# kmetria.net
KiCad netlist of a schematic drawn in Altium Designer
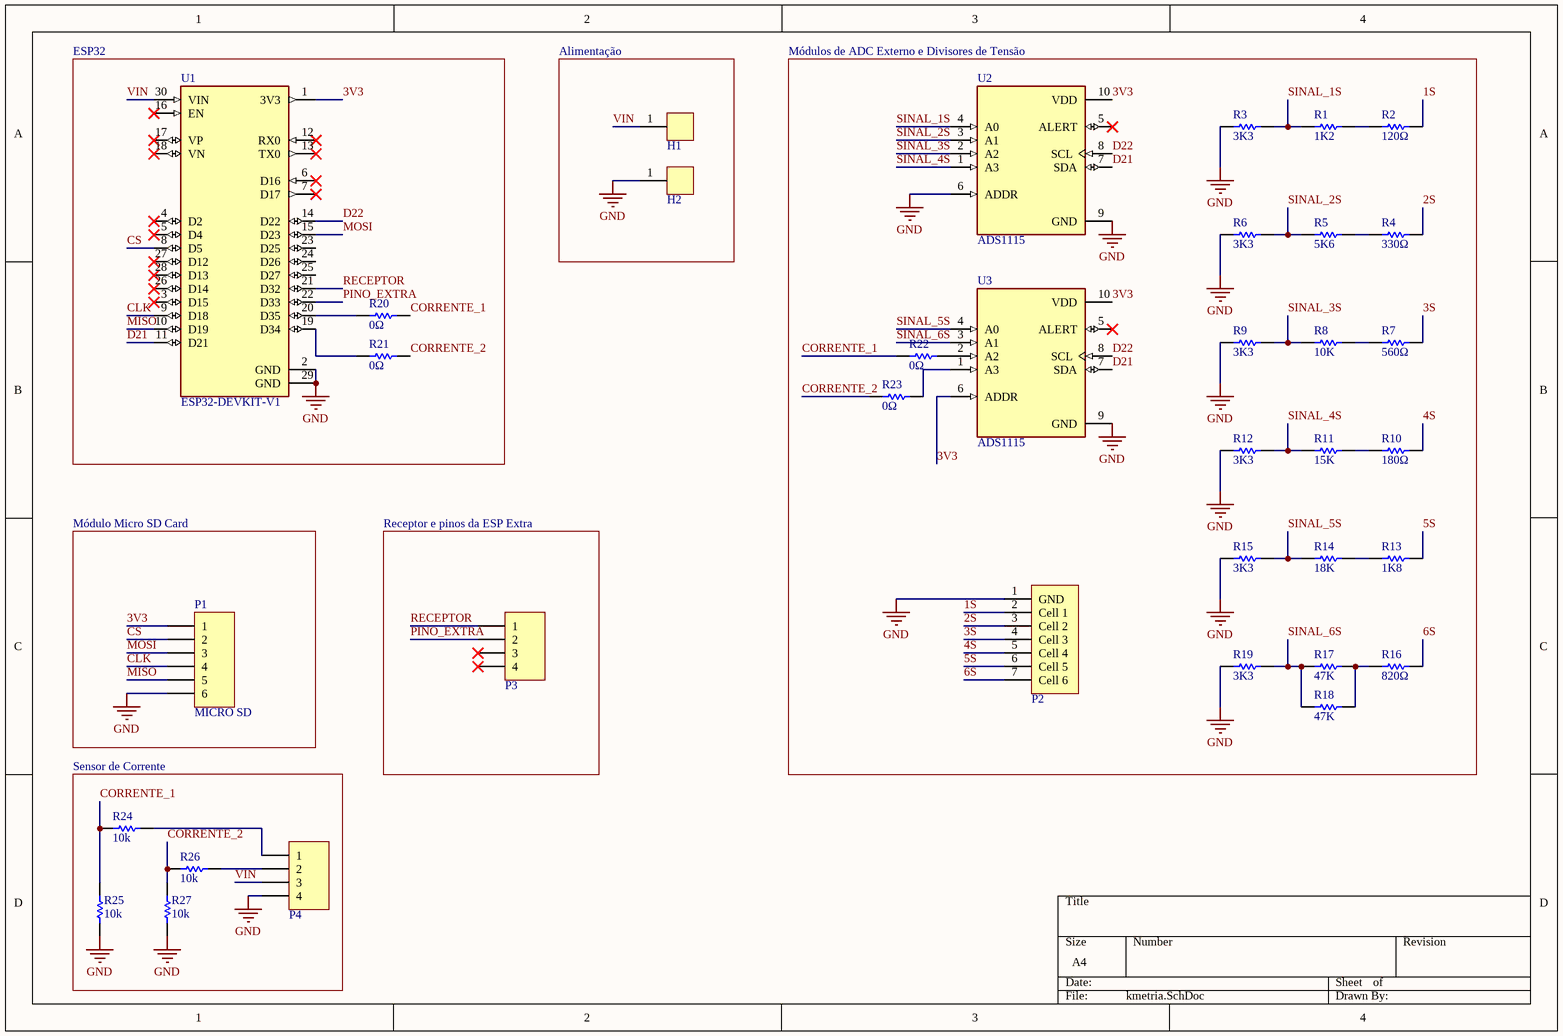
[diagram p0: kmetria.SchDoc]

(export (version "E")
  (design (tool "Eeschema 10.0.6"))
  (components
    (comp (ref "H1")
      (value "Hole")
      (footprint "Hole 1x1")
      (description "General Purpose hole")
      (libsource (lib "kmetria") (part "Hole"))
    )
    (comp (ref "H2")
      (value "Hole")
      (footprint "Hole 1x1")
      (description "General Purpose hole")
      (libsource (lib "kmetria") (part "Hole"))
    )
    (comp (ref "P1")
      (value "MICRO SD")
      (footprint "HDR1X6")
      (description "Headers & Wire Housings 36Pin 2mm Spacing Single Row Hdrs, 5pc")
      (fields
        (field (name "MANUFACTURER") "Molex, LLC")
        (field (name "MANUFACTURER PART NUMBER") "0022284360")
      )
      (libsource (lib "kmetria") (part "Header Male 1x6"))
    )
    (comp (ref "P2")
      (value "Header Male 1x7")
      (footprint "HDR MALE 1x7")
      (description "Headers & Wire Housings 40Pin 2mm Spacing Single Row Hdrs, 5pc")
      (fields (field (name "MANUFACTURER") "Cromax") (field (name "MANUFACTURER PART NUMBER") "IMP10327"))
      (libsource (lib "kmetria") (part "Header Male 1x7"))
    )
    (comp (ref "P3")
      (value "Header 1x4")
      (footprint "HDR MALE 1x4")
      (description "Headers & Wire Housings 40Pin 2mm Spacing Single Row Hdrs, 5pc")
      (fields (field (name "MANUFACTURER") "Cromax") (field (name "MANUFACTURER PART NUMBER") "IMP10327"))
      (libsource (lib "kmetria") (part "Header 1x4"))
    )
    (comp (ref "P4")
      (value "Header 1x4")
      (footprint "HDR MALE 1x4")
      (description "Headers & Wire Housings 40Pin 2mm Spacing Single Row Hdrs, 5pc")
      (fields (field (name "MANUFACTURER") "Cromax") (field (name "MANUFACTURER PART NUMBER") "IMP10327"))
      (libsource (lib "kmetria") (part "Header 1x4"))
    )
    (comp (ref "R1")
      (value "1K2")
      (footprint "RESISTOR 0805")
      (description "RES SMD 5% 0805")
      (fields (field (name "TOLERANCE") "±5%"))
      (libsource (lib "kmetria") (part "RES SMD 5% 0805"))
    )
    (comp (ref "R2")
      (value "120Ω")
      (footprint "RESISTOR 0805")
      (description "RES SMD 5% 0805")
      (fields (field (name "TOLERANCE") "±5%"))
      (libsource (lib "kmetria") (part "RES SMD 5% 0805"))
    )
    (comp (ref "R3")
      (value "3K3")
      (footprint "RESISTOR 0805")
      (description "Thick Film Resistors - SMD 0603 5%")
      (fields
        (field (name "MANUFACTURER") "Yageo")
        (field (name "MANUFACTURER PART NUMBER") "RC0603JR-071R8L")
      )
      (libsource (lib "kmetria") (part "RES 5% 0603"))
    )
    (comp (ref "R4")
      (value "330Ω")
      (footprint "RESISTOR 0805")
      (description "Thick Film Resistors - SMD 0603 5%")
      (fields
        (field (name "MANUFACTURER") "Yageo")
        (field (name "MANUFACTURER PART NUMBER") "RC0603JR-071R8L")
      )
      (libsource (lib "kmetria") (part "RES 5% 0603"))
    )
    (comp (ref "R5")
      (value "5K6")
      (footprint "RESISTOR 0805")
      (description "RES SMD 5% 0805")
      (fields (field (name "TOLERANCE") "±5%"))
      (libsource (lib "kmetria") (part "RES SMD 5% 0805"))
    )
    (comp (ref "R6")
      (value "3K3")
      (footprint "RESISTOR 0805")
      (description "Thick Film Resistors - SMD 0603 5%")
      (fields
        (field (name "MANUFACTURER") "Yageo")
        (field (name "MANUFACTURER PART NUMBER") "RC0603JR-071R8L")
      )
      (libsource (lib "kmetria") (part "RES 5% 0603"))
    )
    (comp (ref "R7")
      (value "560Ω")
      (footprint "RESISTOR 0805")
      (description "RES SMD 5% 0805")
      (fields (field (name "TOLERANCE") "±5%"))
      (libsource (lib "kmetria") (part "RES SMD 5% 0805"))
    )
    (comp (ref "R8")
      (value "10K")
      (footprint "RESISTOR 0805")
      (description "RES SMD 5% 0805")
      (fields (field (name "TOLERANCE") "±5%"))
      (libsource (lib "kmetria") (part "RES SMD 5% 0805"))
    )
    (comp (ref "R9")
      (value "3K3")
      (footprint "RESISTOR 0805")
      (description "Thick Film Resistors - SMD 0603 5%")
      (fields
        (field (name "MANUFACTURER") "Yageo")
        (field (name "MANUFACTURER PART NUMBER") "RC0603JR-071R8L")
      )
      (libsource (lib "kmetria") (part "RES 5% 0603"))
    )
    (comp (ref "R10")
      (value "180Ω")
      (footprint "RESISTOR 0805")
      (description "Thick Film Resistors - SMD 0603 5%")
      (fields
        (field (name "MANUFACTURER") "Yageo")
        (field (name "MANUFACTURER PART NUMBER") "RC0603JR-071R8L")
      )
      (libsource (lib "kmetria") (part "RES 5% 0603"))
    )
    (comp (ref "R11")
      (value "15K")
      (footprint "RESISTOR 0805")
      (description "RES SMD 5% 0805")
      (fields (field (name "TOLERANCE") "±5%"))
      (libsource (lib "kmetria") (part "RES SMD 5% 0805"))
    )
    (comp (ref "R12")
      (value "3K3")
      (footprint "RESISTOR 0805")
      (description "Thick Film Resistors - SMD 0603 5%")
      (fields
        (field (name "MANUFACTURER") "Yageo")
        (field (name "MANUFACTURER PART NUMBER") "RC0603JR-071R8L")
      )
      (libsource (lib "kmetria") (part "RES 5% 0603"))
    )
    (comp (ref "R13")
      (value "1K8")
      (footprint "RESISTOR 0805")
      (description "RES SMD 5% 0805")
      (fields (field (name "TOLERANCE") "±5%"))
      (libsource (lib "kmetria") (part "RES SMD 5% 0805"))
    )
    (comp (ref "R14")
      (value "18K")
      (footprint "RESISTOR 0805")
      (description "Chip Resistor, 1 KOhm, +/- 1%, 0.25 W, -55 to 155 degC, 1206 (3216 Metric)")
      (fields (field (name "Comment") "Resistor 1k +/-1% 1206 250 mW"))
      (libsource (lib "kmetria") (part "RES 1206"))
    )
    (comp (ref "R15")
      (value "3K3")
      (footprint "RESISTOR 0805")
      (description "Thick Film Resistors - SMD 0603 5%")
      (fields
        (field (name "MANUFACTURER") "Yageo")
        (field (name "MANUFACTURER PART NUMBER") "RC0603JR-071R8L")
      )
      (libsource (lib "kmetria") (part "RES 5% 0603"))
    )
    (comp (ref "R16")
      (value "820Ω")
      (footprint "RESISTOR 0805")
      (description "RES SMD 5% 0805")
      (fields (field (name "TOLERANCE") "±5%"))
      (libsource (lib "kmetria") (part "RES SMD 5% 0805"))
    )
    (comp (ref "R17")
      (value "47K")
      (footprint "RESISTOR 0805")
      (description "Thick Film Resistors - SMD 0603 5%")
      (fields
        (field (name "MANUFACTURER") "Yageo")
        (field (name "MANUFACTURER PART NUMBER") "RC0603JR-071R8L")
      )
      (libsource (lib "kmetria") (part "RES 5% 0603"))
    )
    (comp (ref "R18")
      (value "47K")
      (footprint "RESISTOR 0805")
      (description "Thick Film Resistors - SMD 0603 5%")
      (fields
        (field (name "MANUFACTURER") "Yageo")
        (field (name "MANUFACTURER PART NUMBER") "RC0603JR-071R8L")
      )
      (libsource (lib "kmetria") (part "RES 5% 0603"))
    )
    (comp (ref "R19")
      (value "3K3")
      (footprint "RESISTOR 0805")
      (description "Thick Film Resistors - SMD 0603 5%")
      (fields
        (field (name "MANUFACTURER") "Yageo")
        (field (name "MANUFACTURER PART NUMBER") "RC0603JR-071R8L")
      )
      (libsource (lib "kmetria") (part "RES 5% 0603"))
    )
    (comp (ref "R20")
      (value "0Ω")
      (footprint "RESISTOR 0805")
      (description "Thick Film Resistors - SMD 0603 5%")
      (fields
        (field (name "MANUFACTURER") "Yageo")
        (field (name "MANUFACTURER PART NUMBER") "RC0603JR-071R8L")
      )
      (libsource (lib "kmetria") (part "RES 5% 0603"))
    )
    (comp (ref "R21")
      (value "0Ω")
      (footprint "RESISTOR 0805")
      (description "Thick Film Resistors - SMD 0603 5%")
      (fields
        (field (name "MANUFACTURER") "Yageo")
        (field (name "MANUFACTURER PART NUMBER") "RC0603JR-071R8L")
      )
      (libsource (lib "kmetria") (part "RES 5% 0603"))
    )
    (comp (ref "R22")
      (value "0Ω")
      (footprint "RESISTOR 0805")
      (description "Thick Film Resistors - SMD 0603 5%")
      (fields
        (field (name "MANUFACTURER") "Yageo")
        (field (name "MANUFACTURER PART NUMBER") "RC0603JR-071R8L")
      )
      (libsource (lib "kmetria") (part "RES 5% 0603"))
    )
    (comp (ref "R23")
      (value "0Ω")
      (footprint "RESISTOR 0805")
      (description "Thick Film Resistors - SMD 0603 5%")
      (fields
        (field (name "MANUFACTURER") "Yageo")
        (field (name "MANUFACTURER PART NUMBER") "RC0603JR-071R8L")
      )
      (libsource (lib "kmetria") (part "RES 5% 0603"))
    )
    (comp (ref "R24")
      (value "10k")
      (footprint "RESISTOR 0805")
      (description "RES SMD 5% 0805")
      (fields (field (name "TOLERANCE") "±5%"))
      (libsource (lib "kmetria") (part "RES SMD 5% 0805"))
    )
    (comp (ref "R25")
      (value "10k")
      (footprint "RESISTOR 0805")
      (description "RES SMD 5% 0805")
      (fields (field (name "TOLERANCE") "±5%"))
      (libsource (lib "kmetria") (part "RES SMD 5% 0805"))
    )
    (comp (ref "R26")
      (value "10k")
      (footprint "RESISTOR 0805")
      (description "RES SMD 5% 0805")
      (fields (field (name "TOLERANCE") "±5%"))
      (libsource (lib "kmetria") (part "RES SMD 5% 0805"))
    )
    (comp (ref "R27")
      (value "10k")
      (footprint "RESISTOR 0805")
      (description "RES SMD 5% 0805")
      (fields (field (name "TOLERANCE") "±5%"))
      (libsource (lib "kmetria") (part "RES SMD 5% 0805"))
    )
    (comp (ref "U1")
      (value "ESP32-DEVKIT-V1")
      (footprint "MODULE_ESP32_DEVKIT_V1")
      (fields (field (name "MF") "Do it"))
      (libsource (lib "kmetria") (part "ESP32-DEVKIT-V1"))
    )
    (comp (ref "U2")
      (value "ADS1115")
      (footprint "MODULE_ZC261500")
      (description "ADS1115 Module ADC 4 channel with Pro Gain Amplifier for Arduino RPi")
      (fields (field (name "MP") "ZC261500") (field (name "MF") "YKS"))
      (libsource (lib "kmetria") (part "ZC261500"))
    )
    (comp (ref "U3")
      (value "ADS1115")
      (footprint "MODULE_ZC261500")
      (description "ADS1115 Module ADC 4 channel with Pro Gain Amplifier for Arduino RPi")
      (fields (field (name "MP") "ZC261500") (field (name "MF") "YKS"))
      (libsource (lib "kmetria") (part "ZC261500"))
    )
  )
  (nets
    (net (code "1") (name "/1S") (class "Default")
      (node (ref "P2") (pin "2") (pinfunction "Cell_1_2") (pintype "passive"))
      (node (ref "R2") (pin "2") (pinfunction "2_2") (pintype "passive"))
    )
    (net (code "2") (name "/2S") (class "Default")
      (node (ref "P2") (pin "3") (pinfunction "Cell_2_3") (pintype "passive"))
      (node (ref "R4") (pin "2") (pinfunction "2_2") (pintype "passive"))
    )
    (net (code "3") (name "/3S") (class "Default")
      (node (ref "P2") (pin "4") (pinfunction "Cell_3_4") (pintype "power_in"))
      (node (ref "R7") (pin "2") (pinfunction "2_2") (pintype "passive"))
    )
    (net (code "4") (name "/3V3") (class "Default")
      (node (ref "P1") (pin "1") (pinfunction "1_1") (pintype "passive"))
      (node (ref "U1") (pin "1") (pinfunction "3V3_1") (pintype "output"))
      (node (ref "U2") (pin "10") (pinfunction "VDD_10") (pintype "power_in"))
      (node (ref "U3") (pin "10") (pinfunction "VDD_10") (pintype "power_in"))
      (node (ref "U3") (pin "6") (pinfunction "ADDR_6") (pintype "input"))
    )
    (net (code "5") (name "/4S") (class "Default")
      (node (ref "P2") (pin "5") (pinfunction "Cell_4_5") (pintype "power_in"))
      (node (ref "R10") (pin "2") (pinfunction "2_2") (pintype "passive"))
    )
    (net (code "6") (name "/5S") (class "Default")
      (node (ref "P2") (pin "6") (pinfunction "Cell_5_6") (pintype "power_in"))
      (node (ref "R13") (pin "2") (pinfunction "2_2") (pintype "passive"))
    )
    (net (code "7") (name "/6S") (class "Default")
      (node (ref "P2") (pin "7") (pinfunction "Cell_6_7") (pintype "power_in"))
      (node (ref "R16") (pin "2") (pinfunction "2_2") (pintype "passive"))
    )
    (net (code "8") (name "/CLK") (class "Default")
      (node (ref "P1") (pin "4") (pinfunction "4_4") (pintype "passive"))
      (node (ref "U1") (pin "9") (pinfunction "D18_9") (pintype "bidirectional"))
    )
    (net (code "9") (name "/CORRENTE_1") (class "Default")
      (node (ref "R20") (pin "2") (pinfunction "2_2") (pintype "passive"))
      (node (ref "R22") (pin "1") (pinfunction "1_1") (pintype "passive"))
      (node (ref "R24") (pin "1") (pinfunction "1_1") (pintype "passive"))
      (node (ref "R25") (pin "2") (pinfunction "2_2") (pintype "passive"))
    )
    (net (code "10") (name "/CORRENTE_2") (class "Default")
      (node (ref "R21") (pin "2") (pinfunction "2_2") (pintype "passive"))
      (node (ref "R23") (pin "1") (pinfunction "1_1") (pintype "passive"))
      (node (ref "R26") (pin "1") (pinfunction "1_1") (pintype "passive"))
      (node (ref "R27") (pin "2") (pinfunction "2_2") (pintype "passive"))
    )
    (net (code "11") (name "/CS") (class "Default")
      (node (ref "P1") (pin "2") (pinfunction "2_2") (pintype "passive"))
      (node (ref "U1") (pin "8") (pinfunction "D5_8") (pintype "bidirectional"))
    )
    (net (code "12") (name "/D21") (class "Default")
      (node (ref "U1") (pin "11") (pinfunction "D21_11") (pintype "bidirectional"))
      (node (ref "U2") (pin "7") (pinfunction "SDA_7") (pintype "bidirectional"))
      (node (ref "U3") (pin "7") (pinfunction "SDA_7") (pintype "bidirectional"))
    )
    (net (code "13") (name "/D22") (class "Default")
      (node (ref "U1") (pin "14") (pinfunction "D22_14") (pintype "bidirectional"))
      (node (ref "U2") (pin "8") (pinfunction "SCL_8") (pintype "input"))
      (node (ref "U3") (pin "8") (pinfunction "SCL_8") (pintype "input"))
    )
    (net (code "14") (name "/MISO") (class "Default")
      (node (ref "P1") (pin "5") (pinfunction "5_5") (pintype "passive"))
      (node (ref "U1") (pin "10") (pinfunction "D19_10") (pintype "bidirectional"))
    )
    (net (code "15") (name "/MOSI") (class "Default")
      (node (ref "P1") (pin "3") (pinfunction "3_3") (pintype "passive"))
      (node (ref "U1") (pin "15") (pinfunction "D23_15") (pintype "bidirectional"))
    )
    (net (code "16") (name "/PINO_EXTRA") (class "Default")
      (node (ref "P3") (pin "2") (pinfunction "2_2") (pintype "passive"))
      (node (ref "U1") (pin "22") (pinfunction "D33_22") (pintype "bidirectional"))
    )
    (net (code "17") (name "/RECEPTOR") (class "Default")
      (node (ref "P3") (pin "1") (pinfunction "1_1") (pintype "passive"))
      (node (ref "U1") (pin "21") (pinfunction "D32_21") (pintype "bidirectional"))
    )
    (net (code "18") (name "/SINAL_1S") (class "Default")
      (node (ref "R1") (pin "1") (pinfunction "1_1") (pintype "passive"))
      (node (ref "R3") (pin "2") (pinfunction "2_2") (pintype "passive"))
      (node (ref "U2") (pin "4") (pinfunction "A0_4") (pintype "input"))
    )
    (net (code "19") (name "/SINAL_2S") (class "Default")
      (node (ref "R5") (pin "1") (pinfunction "1_1") (pintype "passive"))
      (node (ref "R6") (pin "2") (pinfunction "2_2") (pintype "passive"))
      (node (ref "U2") (pin "3") (pinfunction "A1_3") (pintype "input"))
    )
    (net (code "20") (name "/SINAL_3S") (class "Default")
      (node (ref "R8") (pin "1") (pinfunction "1_1") (pintype "passive"))
      (node (ref "R9") (pin "2") (pinfunction "2_2") (pintype "passive"))
      (node (ref "U2") (pin "2") (pinfunction "A2_2") (pintype "input"))
    )
    (net (code "21") (name "/SINAL_4S") (class "Default")
      (node (ref "R11") (pin "1") (pinfunction "1_1") (pintype "passive"))
      (node (ref "R12") (pin "2") (pinfunction "2_2") (pintype "passive"))
      (node (ref "U2") (pin "1") (pinfunction "A3_1") (pintype "input"))
    )
    (net (code "22") (name "/SINAL_5S") (class "Default")
      (node (ref "R14") (pin "1") (pinfunction "1_1") (pintype "passive"))
      (node (ref "R15") (pin "2") (pinfunction "2_2") (pintype "passive"))
      (node (ref "U3") (pin "4") (pinfunction "A0_4") (pintype "input"))
    )
    (net (code "23") (name "/SINAL_6S") (class "Default")
      (node (ref "R17") (pin "1") (pinfunction "1_1") (pintype "passive"))
      (node (ref "R18") (pin "1") (pinfunction "1_1") (pintype "passive"))
      (node (ref "R19") (pin "2") (pinfunction "2_2") (pintype "passive"))
      (node (ref "U3") (pin "3") (pinfunction "A1_3") (pintype "input"))
    )
    (net (code "24") (name "/VIN") (class "Default")
      (node (ref "H1") (pin "1") (pinfunction "1_1") (pintype "passive"))
      (node (ref "P4") (pin "3") (pinfunction "3_3") (pintype "power_in"))
      (node (ref "U1") (pin "30") (pinfunction "VIN_30") (pintype "input"))
    )
    (net (code "25") (name "GND") (class "Default")
      (node (ref "H2") (pin "1") (pinfunction "1_1") (pintype "passive"))
      (node (ref "P1") (pin "6") (pinfunction "6_6") (pintype "passive"))
      (node (ref "P2") (pin "1") (pinfunction "GND_1") (pintype "passive"))
      (node (ref "P4") (pin "4") (pinfunction "4_4") (pintype "power_in"))
      (node (ref "R12") (pin "1") (pinfunction "1_1") (pintype "passive"))
      (node (ref "R15") (pin "1") (pinfunction "1_1") (pintype "passive"))
      (node (ref "R19") (pin "1") (pinfunction "1_1") (pintype "passive"))
      (node (ref "R25") (pin "1") (pinfunction "1_1") (pintype "passive"))
      (node (ref "R27") (pin "1") (pinfunction "1_1") (pintype "passive"))
      (node (ref "R3") (pin "1") (pinfunction "1_1") (pintype "passive"))
      (node (ref "R6") (pin "1") (pinfunction "1_1") (pintype "passive"))
      (node (ref "R9") (pin "1") (pinfunction "1_1") (pintype "passive"))
      (node (ref "U1") (pin "2") (pinfunction "GND_2") (pintype "power_in"))
      (node (ref "U1") (pin "29") (pinfunction "GND_29") (pintype "power_in"))
      (node (ref "U2") (pin "6") (pinfunction "ADDR_6") (pintype "input"))
      (node (ref "U2") (pin "9") (pinfunction "GND_9") (pintype "power_in"))
      (node (ref "U3") (pin "9") (pinfunction "GND_9") (pintype "power_in"))
    )
    (net (code "26") (name "Net-(P4-Pad1)") (class "Default")
      (node (ref "P4") (pin "1") (pinfunction "1_1") (pintype "passive"))
      (node (ref "R24") (pin "2") (pinfunction "2_2") (pintype "passive"))
    )
    (net (code "27") (name "Net-(P4-Pad2)") (class "Default")
      (node (ref "P4") (pin "2") (pinfunction "2_2") (pintype "passive"))
      (node (ref "R26") (pin "2") (pinfunction "2_2") (pintype "passive"))
    )
    (net (code "28") (name "Net-(R1-Pad2)") (class "Default")
      (node (ref "R1") (pin "2") (pinfunction "2_2") (pintype "passive"))
      (node (ref "R2") (pin "1") (pinfunction "1_1") (pintype "passive"))
    )
    (net (code "29") (name "Net-(R4-Pad1)") (class "Default")
      (node (ref "R4") (pin "1") (pinfunction "1_1") (pintype "passive"))
      (node (ref "R5") (pin "2") (pinfunction "2_2") (pintype "passive"))
    )
    (net (code "30") (name "Net-(R7-Pad1)") (class "Default")
      (node (ref "R7") (pin "1") (pinfunction "1_1") (pintype "passive"))
      (node (ref "R8") (pin "2") (pinfunction "2_2") (pintype "passive"))
    )
    (net (code "31") (name "Net-(R10-Pad1)") (class "Default")
      (node (ref "R10") (pin "1") (pinfunction "1_1") (pintype "passive"))
      (node (ref "R11") (pin "2") (pinfunction "2_2") (pintype "passive"))
    )
    (net (code "32") (name "Net-(R13-Pad1)") (class "Default")
      (node (ref "R13") (pin "1") (pinfunction "1_1") (pintype "passive"))
      (node (ref "R14") (pin "2") (pinfunction "2_2") (pintype "passive"))
    )
    (net (code "33") (name "Net-(R16-Pad1)") (class "Default")
      (node (ref "R16") (pin "1") (pinfunction "1_1") (pintype "passive"))
      (node (ref "R17") (pin "2") (pinfunction "2_2") (pintype "passive"))
      (node (ref "R18") (pin "2") (pinfunction "2_2") (pintype "passive"))
    )
    (net (code "34") (name "Net-(U1-D34)") (class "Default")
      (node (ref "R21") (pin "1") (pinfunction "1_1") (pintype "passive"))
      (node (ref "U1") (pin "19") (pinfunction "D34_19") (pintype "bidirectional"))
    )
    (net (code "35") (name "Net-(U1-D35)") (class "Default")
      (node (ref "R20") (pin "1") (pinfunction "1_1") (pintype "passive"))
      (node (ref "U1") (pin "20") (pinfunction "D35_20") (pintype "bidirectional"))
    )
    (net (code "36") (name "Net-(U3-A2)") (class "Default")
      (node (ref "R22") (pin "2") (pinfunction "2_2") (pintype "passive"))
      (node (ref "U3") (pin "2") (pinfunction "A2_2") (pintype "input"))
    )
    (net (code "37") (name "Net-(U3-A3)") (class "Default")
      (node (ref "R23") (pin "2") (pinfunction "2_2") (pintype "passive"))
      (node (ref "U3") (pin "1") (pinfunction "A3_1") (pintype "input"))
    )
    (net (code "38") (name "unconnected-(P3-Pad3)") (class "Default")
      (node (ref "P3") (pin "3") (pinfunction "3_3") (pintype "power_in+no_connect"))
    )
    (net (code "39") (name "unconnected-(P3-Pad4)") (class "Default")
      (node (ref "P3") (pin "4") (pinfunction "4_4") (pintype "power_in+no_connect"))
    )
    (net (code "40") (name "unconnected-(U1-D2-Pad4)") (class "Default")
      (node (ref "U1") (pin "4") (pinfunction "D2_4") (pintype "bidirectional+no_connect"))
    )
    (net (code "41") (name "unconnected-(U1-D4-Pad5)") (class "Default")
      (node (ref "U1") (pin "5") (pinfunction "D4_5") (pintype "bidirectional+no_connect"))
    )
    (net (code "42") (name "unconnected-(U1-D12-Pad27)") (class "Default")
      (node (ref "U1") (pin "27") (pinfunction "D12_27") (pintype "bidirectional+no_connect"))
    )
    (net (code "43") (name "unconnected-(U1-D13-Pad28)") (class "Default")
      (node (ref "U1") (pin "28") (pinfunction "D13_28") (pintype "bidirectional+no_connect"))
    )
    (net (code "44") (name "unconnected-(U1-D14-Pad26)") (class "Default")
      (node (ref "U1") (pin "26") (pinfunction "D14_26") (pintype "bidirectional+no_connect"))
    )
    (net (code "45") (name "unconnected-(U1-D15-Pad3)") (class "Default")
      (node (ref "U1") (pin "3") (pinfunction "D15_3") (pintype "bidirectional+no_connect"))
    )
    (net (code "46") (name "unconnected-(U1-D16-Pad6)") (class "Default")
      (node (ref "U1") (pin "6") (pinfunction "D16_6") (pintype "input+no_connect"))
    )
    (net (code "47") (name "unconnected-(U1-D17-Pad7)") (class "Default")
      (node (ref "U1") (pin "7") (pinfunction "D17_7") (pintype "output+no_connect"))
    )
    (net (code "48") (name "unconnected-(U1-D25-Pad23)") (class "Default")
      (node (ref "U1") (pin "23") (pinfunction "D25_23") (pintype "bidirectional"))
    )
    (net (code "49") (name "unconnected-(U1-D26-Pad24)") (class "Default")
      (node (ref "U1") (pin "24") (pinfunction "D26_24") (pintype "bidirectional"))
    )
    (net (code "50") (name "unconnected-(U1-D27-Pad25)") (class "Default")
      (node (ref "U1") (pin "25") (pinfunction "D27_25") (pintype "bidirectional"))
    )
    (net (code "51") (name "unconnected-(U1-EN-Pad16)") (class "Default")
      (node (ref "U1") (pin "16") (pinfunction "EN_16") (pintype "input+no_connect"))
    )
    (net (code "52") (name "unconnected-(U1-RX0-Pad12)") (class "Default")
      (node (ref "U1") (pin "12") (pinfunction "RX0_12") (pintype "input+no_connect"))
    )
    (net (code "53") (name "unconnected-(U1-TX0-Pad13)") (class "Default")
      (node (ref "U1") (pin "13") (pinfunction "TX0_13") (pintype "output+no_connect"))
    )
    (net (code "54") (name "unconnected-(U1-VN-Pad18)") (class "Default")
      (node (ref "U1") (pin "18") (pinfunction "VN_18") (pintype "bidirectional+no_connect"))
    )
    (net (code "55") (name "unconnected-(U1-VP-Pad17)") (class "Default")
      (node (ref "U1") (pin "17") (pinfunction "VP_17") (pintype "bidirectional+no_connect"))
    )
    (net (code "56") (name "unconnected-(U2-ALERT-Pad5)") (class "Default")
      (node (ref "U2") (pin "5") (pinfunction "ALERT_5") (pintype "bidirectional+no_connect"))
    )
    (net (code "57") (name "unconnected-(U3-ALERT-Pad5)") (class "Default")
      (node (ref "U3") (pin "5") (pinfunction "ALERT_5") (pintype "bidirectional+no_connect"))
    )
  )
)
